# Board.net
KiCad netlist of a schematic drawn in Altium Designer
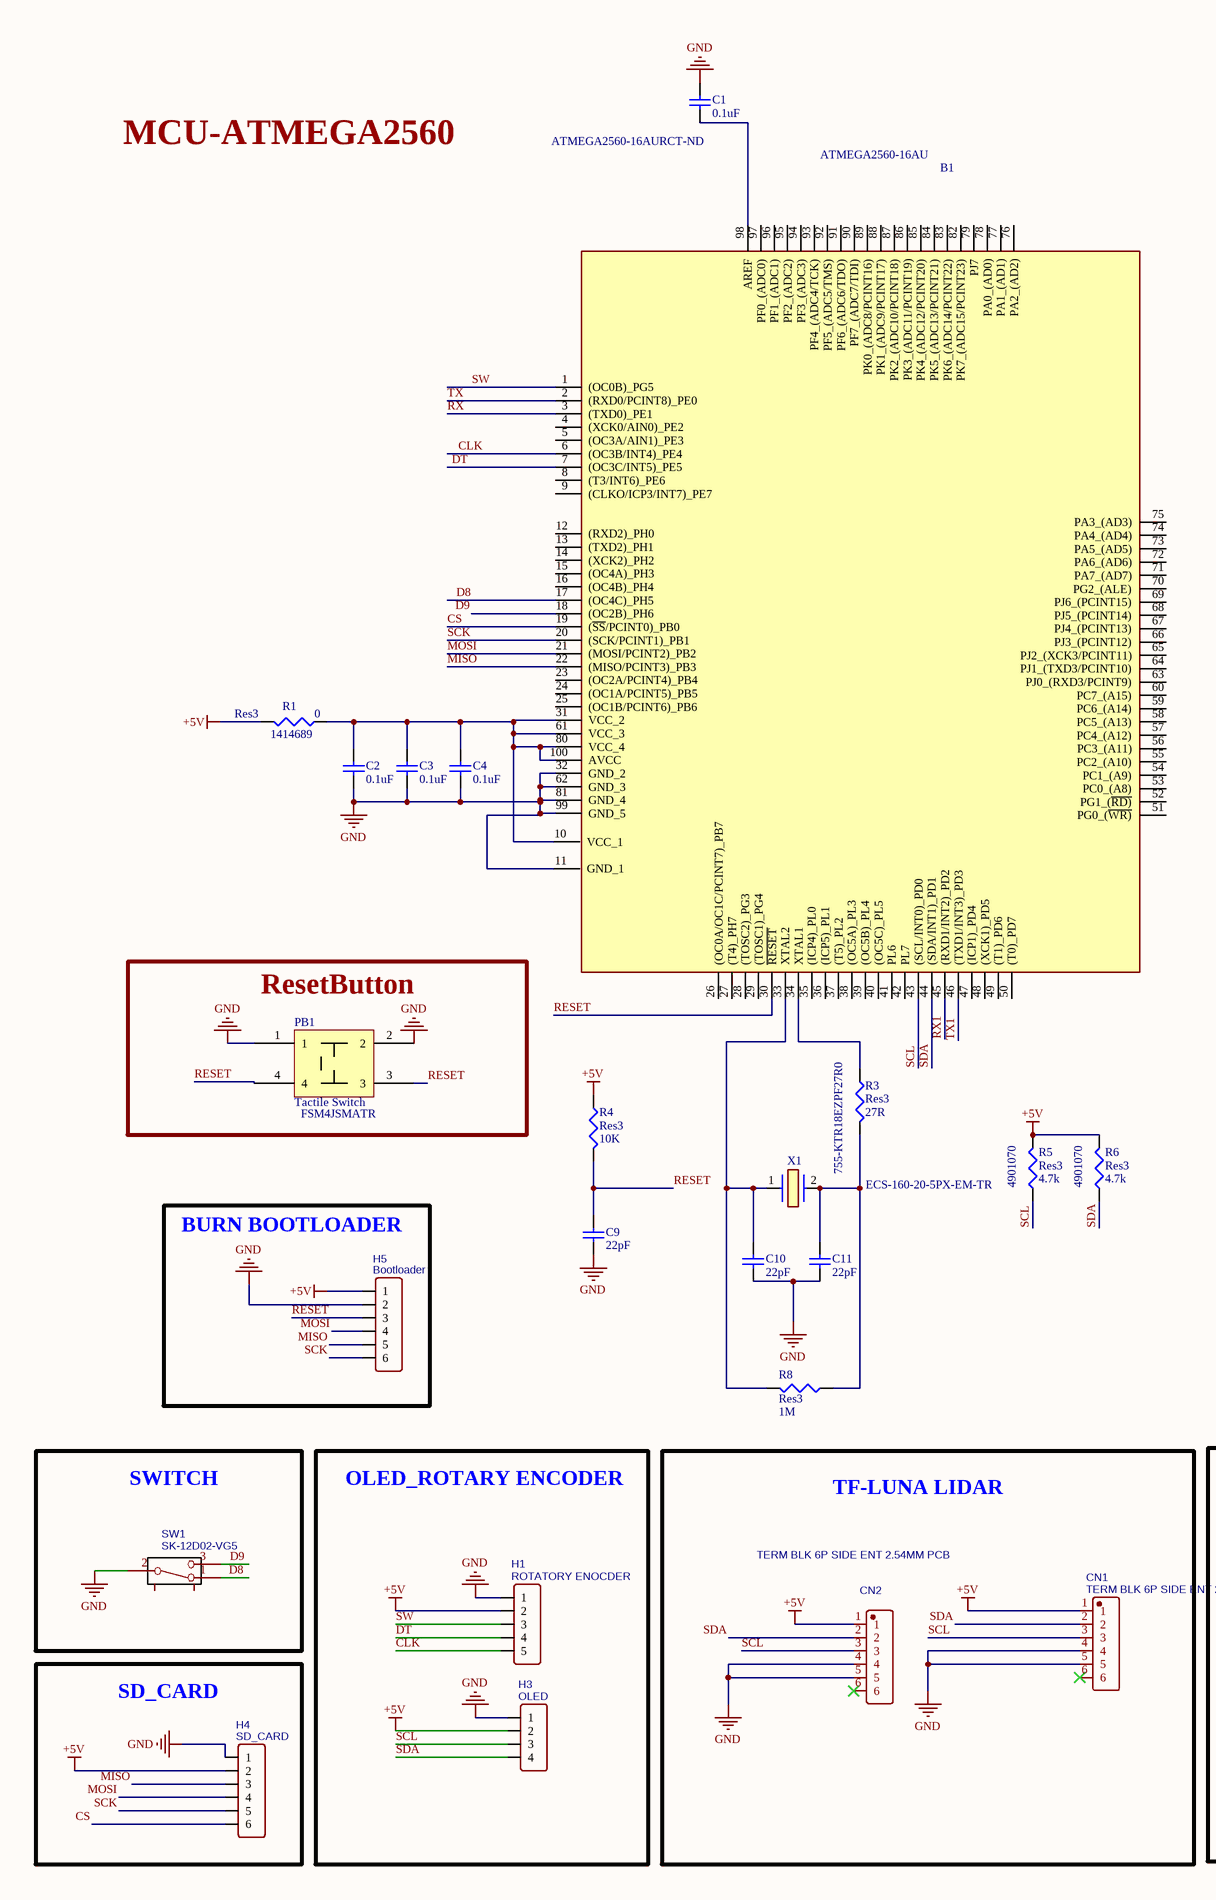
[diagram p0: Board.SchDoc, left]
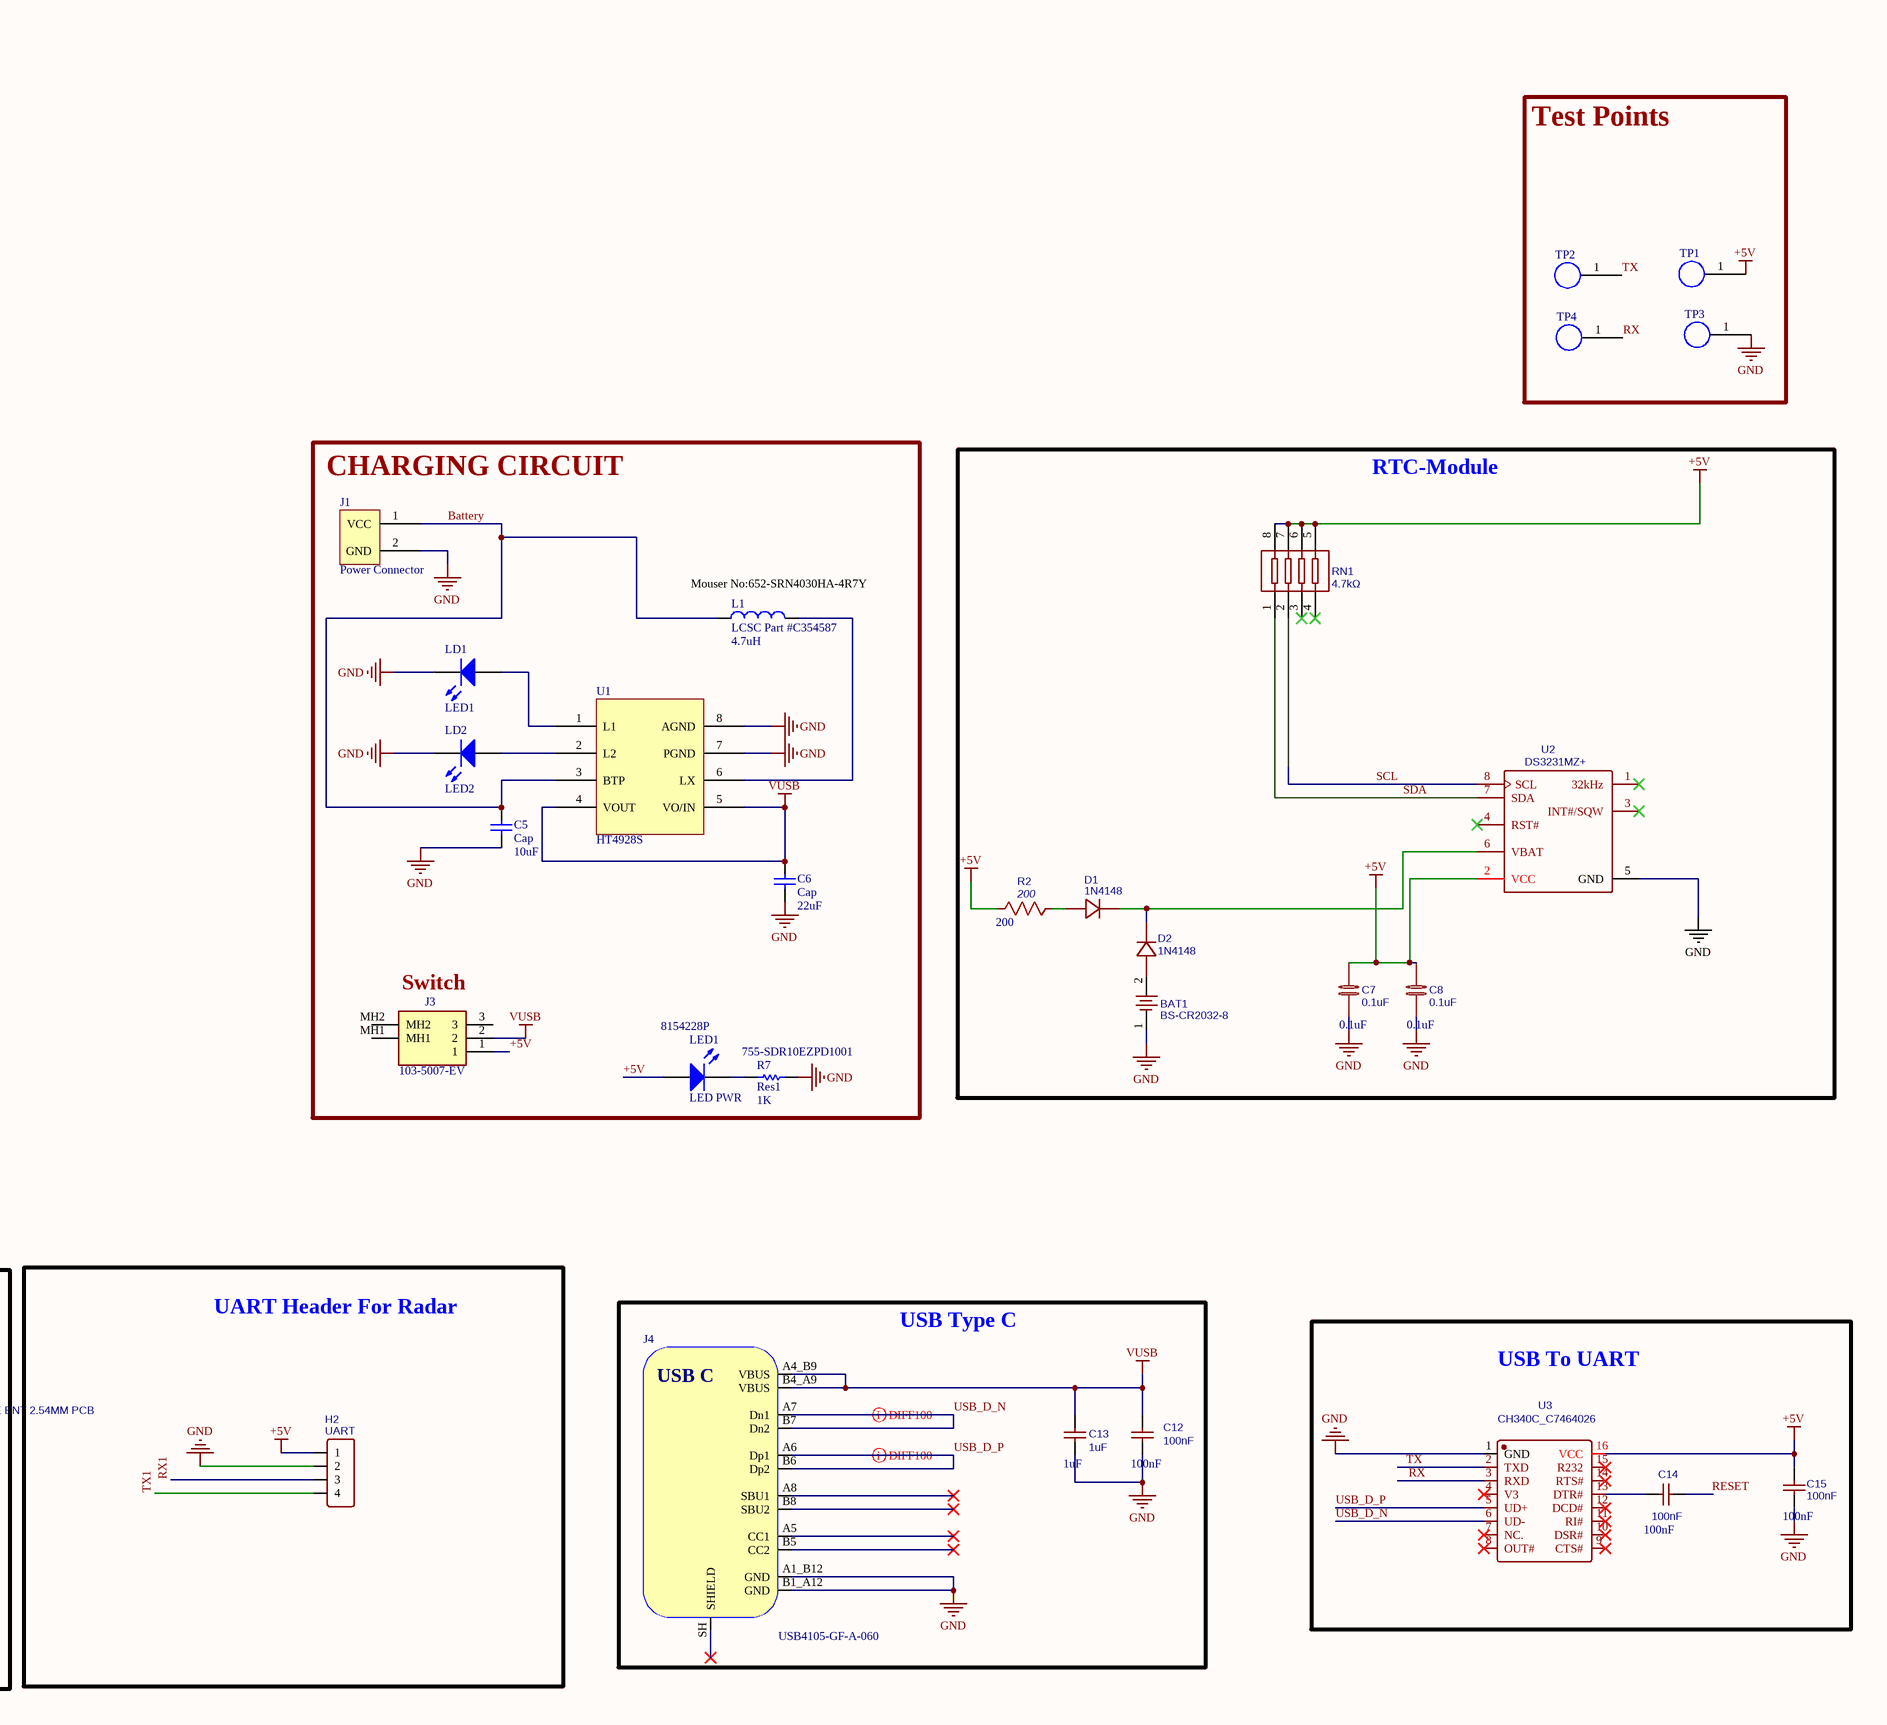
[diagram p1: Board.SchDoc, right]

(export (version "E")
  (design (tool "Eeschema 10.0.6"))
  (components
    (comp (ref "B1")
      (value "ATMEGA2560-16AU")
      (footprint "ATMEGA2560-16AUR")
      (description "AVR ATmega Microcontroller 8-bit 16MHz 256KB FLASH TQFP100")
      (fields
        (field (name "MOUSER PART NUMBER") "556-ATMEGA2560-16AU")
        (field (name "SUPPLIER PART NUMBER 1") "ATMEGA2560-16AURCT-ND")
        (field (name "MANUFACTURER") "Microchip")
      )
      (libsource (lib "aruduino mega_1") (part "ATMEGA2560-16AU"))
    )
    (comp (ref "BAT1")
      (value "BS-CR2032-8")
      (footprint "BS-CR2032-8")
      (fields (field (name "MANUFACTURER") "LX(连欣科技)") (field (name "CONTRIBUTOR") "lcsc"))
      (libsource (lib "altium-import") (part "root_1_BS-CR2032-8_"))
    )
    (comp (ref "C1")
      (value "0.1uF")
      (footprint "CAP 0402")
      (description "Commercial Chip T101 Commercial Tape/reel, 7 Inch Paper Tape")
      (fields
        (field (name "MANUFACTURER") "Kyocera AVX")
        (field (name "MANUFACTURER PART NUMBER") "04023C104KAT2A-62")
      )
      (libsource (lib "Miscellaneous Devices") (part "Cap"))
    )
    (comp (ref "C2")
      (value "0.1uF")
      (footprint "CAP 0402")
      (description "Commercial Chip T101 Commercial Tape/reel, 7 Inch Paper Tape")
      (fields
        (field (name "MANUFACTURER") "Kyocera AVX")
        (field (name "MANUFACTURER PART NUMBER") "04023C104KAT2A-62")
      )
      (libsource (lib "Miscellaneous Devices") (part "Cap"))
    )
    (comp (ref "C3")
      (value "0.1uF")
      (footprint "CAP 0402")
      (description "Commercial Chip T101 Commercial Tape/reel, 7 Inch Paper Tape")
      (fields
        (field (name "MANUFACTURER") "Kyocera AVX")
        (field (name "MANUFACTURER PART NUMBER") "04023C104KAT2A-62")
      )
      (libsource (lib "Miscellaneous Devices") (part "Cap"))
    )
    (comp (ref "C4")
      (value "0.1uF")
      (footprint "CAP 0402")
      (description "Commercial Chip T101 Commercial Tape/reel, 7 Inch Paper Tape")
      (fields
        (field (name "MANUFACTURER") "Kyocera AVX")
        (field (name "MANUFACTURER PART NUMBER") "04023C104KAT2A-62")
      )
      (libsource (lib "Miscellaneous Devices") (part "Cap"))
    )
    (comp (ref "C5")
      (value "Cap")
      (footprint "Cap_0603")
      (description "Capacitor")
      (fields (field (name "ALTIUM_VALUE") "10uF") (field (name "PUBLISHER") "Altium Limited"))
      (libsource (lib "Miscellaneous Devices") (part "Cap"))
    )
    (comp (ref "C6")
      (value "Cap")
      (footprint "CAP 1206")
      (description "Capacitor")
      (fields (field (name "ALTIUM_VALUE") "22uF") (field (name "PUBLISHER") "Altium Limited"))
      (libsource (lib "Miscellaneous Devices") (part "Cap"))
    )
    (comp (ref "C7")
      (value "0.1uF")
      (footprint "CAP_0805")
      (fields
        (field (name "MANUFACTURER PART") "CGA4J3X7T2E104KT0Y0N")
        (field (name "MANUFACTURER") "TDK")
        (field (name "ALTIUM_VALUE") "0.1uF")
        (field (name "CONTRIBUTOR") "LCEDA_Lib")
      )
      (libsource (lib "altium-import") (part "root_1_0.1uF_"))
    )
    (comp (ref "C8")
      (value "0.1uF")
      (footprint "CAP_0805")
      (fields
        (field (name "MANUFACTURER PART") "CGA4J3X7T2E104KT0Y0N")
        (field (name "MANUFACTURER") "TDK")
        (field (name "ALTIUM_VALUE") "0.1uF")
        (field (name "CONTRIBUTOR") "LCEDA_Lib")
      )
      (libsource (lib "altium-import") (part "root_1_0.1uF_"))
    )
    (comp (ref "C9")
      (value "22pF")
      (footprint "CAP 1206")
      (description "22.0Pf 50.0V Rohs Compliant: Yes")
      (fields
        (field (name "MANUFACTURER") "KEMET")
        (field (name "MANUFACTURER PART NUMBER") "C1206C220K5GAC7210")
      )
      (libsource (lib "Miscellaneous Devices") (part "Cap"))
    )
    (comp (ref "C10")
      (value "22pF")
      (footprint "CAP 1206")
      (description "22.0Pf 50.0V Rohs Compliant: Yes")
      (fields
        (field (name "MANUFACTURER") "KEMET")
        (field (name "MANUFACTURER PART NUMBER") "C1206C220K5GAC7210")
      )
      (libsource (lib "Miscellaneous Devices") (part "Cap"))
    )
    (comp (ref "C11")
      (value "22pF")
      (footprint "CAP 1206")
      (description "22.0Pf 50.0V Rohs Compliant: Yes")
      (fields
        (field (name "MANUFACTURER") "KEMET")
        (field (name "MANUFACTURER PART NUMBER") "C1206C220K5GAC7210")
      )
      (libsource (lib "Miscellaneous Devices") (part "Cap"))
    )
    (comp (ref "C12")
      (value "100nF")
      (footprint "Cap_0603")
      (fields
        (field (name "MANUFACTURER PART") "0603B104K160")
        (field (name "MANUFACTURER") "WTC")
        (field (name "ALTIUM_VALUE") "100nF")
      )
      (libsource (lib "altium-import") (part "root_1_100nF_"))
    )
    (comp (ref "C13")
      (value "1uF")
      (footprint "Cap_0603")
      (fields
        (field (name "MANUFACTURER PART") "CL10A105KB8NNNC")
        (field (name "MANUFACTURER") "SAMSUNG")
        (field (name "ALTIUM_VALUE") "1uF")
      )
      (libsource (lib "altium-import") (part "root_1_1uF_"))
    )
    (comp (ref "C14")
      (value "100nF")
      (footprint "Cap_0603")
      (fields
        (field (name "MANUFACTURER PART") "0603B104K160")
        (field (name "MANUFACTURER") "WTC")
        (field (name "ALTIUM_VALUE") "100nF")
      )
      (libsource (lib "altium-import") (part "root_0_100nF_"))
    )
    (comp (ref "C15")
      (value "100nF")
      (footprint "Cap_0603")
      (fields
        (field (name "MANUFACTURER PART") "0603B104K160")
        (field (name "MANUFACTURER") "WTC")
        (field (name "ALTIUM_VALUE") "100nF")
      )
      (libsource (lib "altium-import") (part "root_3_100nF_"))
    )
    (comp (ref "CN1")
      (value "TERM BLK 6P SIDE ENT 2.54MM PCB")
      (footprint "1725698")
      (fields
        (field (name "MANUFACTURER") "Phoenix Contact")
        (field (name "MANUFACTURER PART") "1725698")
        (field (name "CONTRIBUTOR") "waqasalivicky123")
      )
      (libsource (lib "altium-import") (part "root_3_6 pin JST_"))
    )
    (comp (ref "CN2")
      (value "TERM BLK 6P SIDE ENT 2.54MM PCB")
      (footprint "1725698")
      (fields
        (field (name "MANUFACTURER") "Phoenix Contact")
        (field (name "MANUFACTURER PART") "1725698")
        (field (name "CONTRIBUTOR") "waqasalivicky123")
      )
      (libsource (lib "altium-import") (part "root_3_6 pin JST_"))
    )
    (comp (ref "D1")
      (value "1N4148")
      (footprint "1N4148WS")
      (fields (field (name "MANUFACTURER") "LJ(朗捷)") (field (name "CONTRIBUTOR") "lcsc"))
      (libsource (lib "altium-import") (part "root_0_1N4148_C18195411_"))
    )
    (comp (ref "D2")
      (value "1N4148")
      (footprint "1N4148WS")
      (fields (field (name "MANUFACTURER") "LJ(朗捷)") (field (name "CONTRIBUTOR") "lcsc"))
      (libsource (lib "altium-import") (part "root_1_1N4148_C18195411_"))
    )
    (comp (ref "H1")
      (value "ROTATORY ENOCDER")
      (footprint "HDR 1X5")
      (fields (field (name "CONTRIBUTOR") "LCEDA_Lib"))
      (libsource (lib "altium-import") (part "root_0_ROTATORY ENOCDER_"))
    )
    (comp (ref "H2")
      (value "UART")
      (footprint "H2")
      (fields (field (name "CONTRIBUTOR") "LCEDA_Lib"))
      (libsource (lib "altium-import") (part "root_0_OLED_"))
    )
    (comp (ref "H3")
      (value "OLED")
      (footprint "HDR 1X4")
      (fields (field (name "CONTRIBUTOR") "LCEDA_Lib"))
      (libsource (lib "altium-import") (part "root_0_OLED_"))
    )
    (comp (ref "H4")
      (value "SD_CARD")
      (footprint "HDR 1X6")
      (fields (field (name "CONTRIBUTOR") "LCEDA_Lib"))
      (libsource (lib "altium-import") (part "root_0_SD_CARD_"))
    )
    (comp (ref "H5")
      (value "Bootloader")
      (footprint "HDR 1X6")
      (fields (field (name "CONTRIBUTOR") "LCEDA_Lib"))
      (libsource (lib "altium-import") (part "root_0_SD_CARD_"))
    )
    (comp (ref "J1")
      (value "Power Connector")
      (footprint "1725656")
      (description "TERM BLK 2P SIDE ENT 2.54MM PCB")
      (fields (field (name "MANUFACTURER") "Phoenix Contact"))
      (libsource (lib "Schlib1") (part "Power Connector"))
    )
    (comp (ref "J3")
      (value "103-5007-EV")
      (footprint "1035007EV")
      (description "Switch")
      (libsource (lib "*") (part "103-5007-EV"))
    )
    (comp (ref "J4")
      (value "USB4105-GF-A-060")
      (footprint "USB4105GFA060")
      (description "USB Connector Type C SMT 12 Pin")
      (fields (field (name "MANUFACTURER") "GCT"))
      (libsource (lib "Schematic-Lib-PhilsLab") (part "USB4105-GF-A-060"))
    )
    (comp (ref "L1")
      (value "LCSC Part #C354587")
      (footprint "L1")
      (description "Inductor")
      (fields (field (name "ALTIUM_VALUE") "4.7uH") (field (name "PUBLISHER") "Altium Limited"))
      (libsource (lib "Miscellaneous Devices") (part "Inductor"))
    )
    (comp (ref "LD1")
      (value "LED1")
      (footprint "0603-LED")
      (description "Typical RED, GREEN, YELLOW, AMBER GaAs LED")
      (fields (field (name "PUBLISHER") "Altium Limited"))
      (libsource (lib "Miscellaneous Devices") (part "LED2"))
    )
    (comp (ref "LD2")
      (value "LED2")
      (footprint "0603-LED")
      (description "Typical RED, GREEN, YELLOW, AMBER GaAs LED")
      (fields (field (name "PUBLISHER") "Altium Limited"))
      (libsource (lib "Miscellaneous Devices") (part "LED2"))
    )
    (comp (ref "LED1")
      (value "LED PWR")
      (footprint "0603-LED")
      (description "Led, Blue, 470 Nm, 3.2 V, 30 Ma, 145 Mcd Rohs Compliant: Yes ¦Wurth Elektronik 150080BS75000")
      (fields
        (field (name "SUPPLIER PART NUMBER 1") "8154228P")
        (field (name "MANUFACTURER") "Wurth Electronics")
        (field (name "MANUFACTURER PART NUMBER") "150080BS75000")
        (field (name "PUBLISHER") "Altium Limited")
      )
      (libsource (lib "Miscellaneous Devices") (part "LED0"))
    )
    (comp (ref "PB1")
      (value "Tactile Switch")
      (footprint "PB1")
      (description "Switch Tactile OFF (ON) SPST Round Button Gull Wing 0.05A 24VDC 1.57N SMD T/R")
      (fields
        (field (name "SUPPLIER PART NUMBER 1") "FSM4JSMATR")
        (field (name "MANUFACTURER") "TE Connectivity Alcoswitch")
        (field (name "MANUFACTURER PART NUMBER") "FSM4JSMATR")
      )
      (libsource (lib "CoinAccepter_1") (part "Tactile Switch"))
    )
    (comp (ref "R1")
      (value "Res3")
      (footprint "1206-res")
      (description "RES SMD 0 OHM JUMPER 1/4W 1206")
      (fields
        (field (name "ALTIUM_VALUE") "0")
        (field (name "SUPPLIER PART NUMBER 1") "1414689")
        (field (name "MANUFACTURER") "Yageo")
        (field (name "MANUFACTURER PART NUMBER") "RC1206JR-070RL")
        (field (name "PUBLISHER") "Altium Limited")
      )
      (libsource (lib "Miscellaneous Devices") (part "Res3"))
    )
    (comp (ref "R2")
      (value "200")
      (footprint "Res_0805")
      (fields
        (field (name "MANUFACTURER PART") "PTFR0805Q200RN9")
        (field (name "MANUFACTURER") "RESI(开步睿思)")
        (field (name "ALTIUM_VALUE") "200")
        (field (name "CONTRIBUTOR") "LCEDA_Lib")
      )
      (libsource (lib "altium-import") (part "root_0_200_"))
    )
    (comp (ref "R3")
      (value "Res3")
      (footprint "1206-res")
      (description "Res Thick Film 1206 27 Ohm 1% 0.25W(1/4W) ±100ppm/C Pad SMD Automotive T/R")
      (fields
        (field (name "ALTIUM_VALUE") "27R")
        (field (name "SUPPLIER PART NUMBER 1") "755-KTR18EZPF27R0")
        (field (name "MANUFACTURER") "Rohm")
        (field (name "MANUFACTURER PART NUMBER") "KTR18EZPF27R0")
      )
      (libsource (lib "Miscellaneous Devices") (part "Res3"))
    )
    (comp (ref "R4")
      (value "Res3")
      (footprint "1206-res")
      (description "Lead Free Chip Resistor Thick Film 1206 10kOhm 5% Paper T/R")
      (fields
        (field (name "ALTIUM_VALUE") "10K")
        (field (name "MANUFACTURER") "Yageo")
        (field (name "MANUFACTURER PART NUMBER") "RC1206JR-0710KP")
      )
      (libsource (lib "Miscellaneous Devices") (part "Res3"))
    )
    (comp (ref "R5")
      (value "Res3")
      (footprint "1206-res")
      (description "Res Thick Film 1206 4.7K Ohm 5% 1/4W ¦100ppm/¦C SMD Paper T/R")
      (fields
        (field (name "ALTIUM_VALUE") "4.7k")
        (field (name "SUPPLIER PART NUMBER 1") "4901070")
        (field (name "MANUFACTURER") "Yageo")
        (field (name "MANUFACTURER PART NUMBER") "RC1206JR-074K7L")
      )
      (libsource (lib "Miscellaneous Devices") (part "Res3"))
    )
    (comp (ref "R6")
      (value "Res3")
      (footprint "1206-res")
      (description "Res Thick Film 1206 4.7K Ohm 5% 1/4W ¦100ppm/¦C SMD Paper T/R")
      (fields
        (field (name "ALTIUM_VALUE") "4.7k")
        (field (name "SUPPLIER PART NUMBER 1") "4901070")
        (field (name "MANUFACTURER") "Yageo")
        (field (name "MANUFACTURER PART NUMBER") "RC1206JR-074K7L")
      )
      (libsource (lib "Miscellaneous Devices") (part "Res3"))
    )
    (comp (ref "R7")
      (value "Res1")
      (footprint "Res_0805")
      (description "Resistor")
      (fields
        (field (name "ALTIUM_VALUE") "1K")
        (field (name "SUPPLIER PART NUMBER 1") "755-SDR10EZPD1001")
        (field (name "MANUFACTURER") "Rohm")
        (field (name "MANUFACTURER PART NUMBER") "SDR10EZPD1001")
        (field (name "PUBLISHER") "Altium Limited")
      )
      (libsource (lib "Miscellaneous Devices") (part "Res1"))
    )
    (comp (ref "R8")
      (value "Res3")
      (footprint "1206-res")
      (description "Res Thick Film 1206 1M Ohm 5% 0.25W(1/4W) ±100ppm/C Pad SMD Automotive T/R")
      (fields
        (field (name "ALTIUM_VALUE") "1M")
        (field (name "MANUFACTURER") "Yageo")
        (field (name "MANUFACTURER PART NUMBER") "AC1206JR-071ML")
      )
      (libsource (lib "Miscellaneous Devices") (part "Res3"))
    )
    (comp (ref "RN1")
      (value "4.7kΩ")
      (footprint "WA04X472JTL")
      (fields
        (field (name "MANUFACTURER") "Walsin(华新科)")
        (field (name "MANUFACTURER PART") "WA04X472JTL")
        (field (name "CONTRIBUTOR") "LCSC")
      )
      (libsource (lib "altium-import") (part "root_0_4.7kΩ_"))
    )
    (comp (ref "SW1")
      (value "SK-12D02-VG5")
      (footprint "SK12D02GA42S")
      (fields (field (name "MANUFACTURER") "韩国韩荣") (field (name "CONTRIBUTOR") "LCSC"))
      (libsource (lib "altium-import") (part "root_0_SK-12D02-VG5_"))
    )
    (comp (ref "TP1") (value "~") (footprint "TP") (libsource (lib "TestPoint") (part "Component_1")))
    (comp (ref "TP2") (value "~") (footprint "TP") (libsource (lib "TestPoint") (part "Component_1")))
    (comp (ref "TP3") (value "~") (footprint "TP") (libsource (lib "TestPoint") (part "Component_1")))
    (comp (ref "TP4") (value "~") (footprint "TP") (libsource (lib "TestPoint") (part "Component_1")))
    (comp (ref "U1")
      (value "HT4928S")
      (footprint "DS3231MZ+TRL")
      (libsource (lib "Schlib1") (part "HT4928S"))
    )
    (comp (ref "U2")
      (value "DS3231MZ+")
      (footprint "DS3231MZ+TRL")
      (fields
        (field (name "MANUFACTURER") "ADI(亚德诺)/MAXIM(美信)")
        (field (name "MANUFACTURER PART") "DS3231MZ+TRL")
      )
      (libsource (lib "altium-import") (part "root_0_DS3231MZ+_"))
    )
    (comp (ref "U3")
      (value "CH340C_C7464026")
      (footprint "CH340C")
      (fields
        (field (name "MANUFACTURER") "WCH(南京沁恒)")
        (field (name "MANUFACTURER PART") "CH340C")
        (field (name "CONTRIBUTOR") "lcsc")
      )
      (libsource (lib "altium-import") (part "root_0_CH340C_C7464026_"))
    )
    (comp (ref "X1")
      (value "ECS-160-20-5PX-EM-TR")
      (footprint "X1")
      (description "Crystal 16.0000MHZ 20PF SMD")
      (fields (field (name "MANUFACTURER") "ECS International"))
      (libsource (lib "*") (part "ABS05-32.768KHZ-6-T"))
    )
  )
  (nets
    (net (code "1") (name "+5V") (class "Default")
      (node (ref "C15") (pin "1") (pinfunction "1_1") (pintype "passive"))
      (node (ref "C7") (pin "2") (pinfunction "2_2") (pintype "passive"))
      (node (ref "C8") (pin "2") (pinfunction "2_2") (pintype "passive"))
      (node (ref "CN1") (pin "1") (pinfunction "1_1") (pintype "passive"))
      (node (ref "CN2") (pin "1") (pinfunction "1_1") (pintype "passive"))
      (node (ref "H1") (pin "2") (pinfunction "2_2") (pintype "passive"))
      (node (ref "H2") (pin "1") (pinfunction "1_1") (pintype "passive"))
      (node (ref "H3") (pin "2") (pinfunction "2_2") (pintype "passive"))
      (node (ref "H4") (pin "2") (pinfunction "2_2") (pintype "passive"))
      (node (ref "H5") (pin "1") (pinfunction "1_1") (pintype "passive"))
      (node (ref "J3") (pin "1") (pinfunction "1_1") (pintype "passive"))
      (node (ref "LED1") (pin "1") (pinfunction "A_1") (pintype "passive"))
      (node (ref "R1") (pin "2") (pinfunction "2_2") (pintype "passive"))
      (node (ref "R2") (pin "1") (pinfunction "1_1") (pintype "passive"))
      (node (ref "R4") (pin "1") (pinfunction "1_1") (pintype "passive"))
      (node (ref "R5") (pin "2") (pinfunction "2_2") (pintype "passive"))
      (node (ref "R6") (pin "2") (pinfunction "2_2") (pintype "passive"))
      (node (ref "RN1") (pin "5") (pinfunction "5_5") (pintype "passive"))
      (node (ref "RN1") (pin "6") (pinfunction "6_6") (pintype "passive"))
      (node (ref "RN1") (pin "7") (pinfunction "7_7") (pintype "passive"))
      (node (ref "RN1") (pin "8") (pinfunction "8_8") (pintype "passive"))
      (node (ref "TP1") (pin "1") (pinfunction "TP_1") (pintype "passive"))
      (node (ref "U2") (pin "2") (pinfunction "VCC_2") (pintype "passive"))
      (node (ref "U3") (pin "16") (pinfunction "VCC_16") (pintype "passive"))
    )
    (net (code "2") (name "/Battery") (class "Default")
      (node (ref "C5") (pin "1") (pinfunction "1_1") (pintype "passive"))
      (node (ref "J1") (pin "1") (pinfunction "VCC_1") (pintype "passive"))
      (node (ref "L1") (pin "1") (pinfunction "1_1") (pintype "passive"))
      (node (ref "U1") (pin "3") (pinfunction "BTP_3") (pintype "passive"))
    )
    (net (code "3") (name "/CLK") (class "Default")
      (node (ref "B1") (pin "6") (pinfunction "(OC3B/INT4)_PE4_6") (pintype "passive"))
      (node (ref "H1") (pin "5") (pinfunction "5_5") (pintype "passive"))
    )
    (net (code "4") (name "/CS") (class "Default")
      (node (ref "B1") (pin "19") (pinfunction "(~{SS}/PCINT0)_PB0_19") (pintype "passive"))
      (node (ref "H4") (pin "6") (pinfunction "6_6") (pintype "passive"))
    )
    (net (code "5") (name "/D8") (class "Default")
      (node (ref "B1") (pin "17") (pinfunction "(OC4C)_PH5_17") (pintype "passive"))
      (node (ref "SW1") (pin "1") (pinfunction "1_1") (pintype "passive"))
    )
    (net (code "6") (name "/D9") (class "Default")
      (node (ref "B1") (pin "18") (pinfunction "(OC2B)_PH6_18") (pintype "passive"))
      (node (ref "SW1") (pin "3") (pinfunction "3_3") (pintype "passive"))
    )
    (net (code "7") (name "/DT") (class "Default")
      (node (ref "B1") (pin "7") (pinfunction "(OC3C/INT5)_PE5_7") (pintype "passive"))
      (node (ref "H1") (pin "4") (pinfunction "4_4") (pintype "passive"))
    )
    (net (code "8") (name "/MISO") (class "Default")
      (node (ref "B1") (pin "22") (pinfunction "(MISO/PCINT3)_PB3_22") (pintype "passive"))
      (node (ref "H4") (pin "3") (pinfunction "3_3") (pintype "passive"))
      (node (ref "H5") (pin "5") (pinfunction "5_5") (pintype "passive"))
    )
    (net (code "9") (name "/MOSI") (class "Default")
      (node (ref "B1") (pin "21") (pinfunction "(MOSI/PCINT2)_PB2_21") (pintype "passive"))
      (node (ref "H4") (pin "4") (pinfunction "4_4") (pintype "passive"))
      (node (ref "H5") (pin "4") (pinfunction "4_4") (pintype "passive"))
    )
    (net (code "10") (name "/RESET") (class "Default")
      (node (ref "B1") (pin "30") (pinfunction "~{RESET}_30") (pintype "passive"))
      (node (ref "C14") (pin "2") (pinfunction "2_2") (pintype "passive"))
      (node (ref "C9") (pin "1") (pinfunction "1_1") (pintype "passive"))
      (node (ref "H5") (pin "3") (pinfunction "3_3") (pintype "passive"))
      (node (ref "PB1") (pin "3") (pinfunction "3_3") (pintype "passive"))
      (node (ref "PB1") (pin "4") (pinfunction "4_4") (pintype "passive"))
      (node (ref "R4") (pin "2") (pinfunction "2_2") (pintype "passive"))
    )
    (net (code "11") (name "/RX") (class "Default")
      (node (ref "B1") (pin "3") (pinfunction "(TXD0)_PE1_3") (pintype "passive"))
      (node (ref "TP4") (pin "1") (pinfunction "TP_1") (pintype "passive"))
      (node (ref "U3") (pin "3") (pinfunction "RXD_3") (pintype "passive"))
    )
    (net (code "12") (name "/RX1") (class "Default")
      (node (ref "B1") (pin "45") (pinfunction "(RXD1/INT2)_PD2_45") (pintype "passive"))
      (node (ref "H2") (pin "3") (pinfunction "3_3") (pintype "passive"))
    )
    (net (code "13") (name "/SCK") (class "Default")
      (node (ref "B1") (pin "20") (pinfunction "(SCK/PCINT1)_PB1_20") (pintype "passive"))
      (node (ref "H4") (pin "5") (pinfunction "5_5") (pintype "passive"))
      (node (ref "H5") (pin "6") (pinfunction "6_6") (pintype "passive"))
    )
    (net (code "14") (name "/SCL") (class "Default")
      (node (ref "B1") (pin "43") (pinfunction "(SCL/INT0)_PD0_43") (pintype "passive"))
      (node (ref "CN1") (pin "3") (pinfunction "3_3") (pintype "passive"))
      (node (ref "CN2") (pin "3") (pinfunction "3_3") (pintype "passive"))
      (node (ref "H3") (pin "3") (pinfunction "3_3") (pintype "passive"))
      (node (ref "R5") (pin "1") (pinfunction "1_1") (pintype "passive"))
      (node (ref "RN1") (pin "2") (pinfunction "2_2") (pintype "passive"))
      (node (ref "U2") (pin "8") (pinfunction "SCL_8") (pintype "passive"))
    )
    (net (code "15") (name "/SDA") (class "Default")
      (node (ref "B1") (pin "44") (pinfunction "(SDA/INT1)_PD1_44") (pintype "passive"))
      (node (ref "CN1") (pin "2") (pinfunction "2_2") (pintype "passive"))
      (node (ref "CN2") (pin "2") (pinfunction "2_2") (pintype "passive"))
      (node (ref "H3") (pin "4") (pinfunction "4_4") (pintype "passive"))
      (node (ref "R6") (pin "1") (pinfunction "1_1") (pintype "passive"))
      (node (ref "RN1") (pin "1") (pinfunction "1_1") (pintype "passive"))
      (node (ref "U2") (pin "7") (pinfunction "SDA_7") (pintype "passive"))
    )
    (net (code "16") (name "/SW") (class "Default")
      (node (ref "B1") (pin "1") (pinfunction "(OC0B)_PG5_1") (pintype "passive"))
      (node (ref "H1") (pin "3") (pinfunction "3_3") (pintype "passive"))
    )
    (net (code "17") (name "/TX") (class "Default")
      (node (ref "B1") (pin "2") (pinfunction "(RXD0/PCINT8)_PE0_2") (pintype "passive"))
      (node (ref "TP2") (pin "1") (pinfunction "TP_1") (pintype "passive"))
      (node (ref "U3") (pin "2") (pinfunction "TXD_2") (pintype "passive"))
    )
    (net (code "18") (name "/TX1") (class "Default")
      (node (ref "B1") (pin "46") (pinfunction "(TXD1/INT3)_PD3_46") (pintype "passive"))
      (node (ref "H2") (pin "4") (pinfunction "4_4") (pintype "passive"))
    )
    (net (code "19") (name "/USB_D_N") (class "Default")
      (node (ref "J4") (pin "A7") (pinfunction "Dn1_A7") (pintype "passive"))
      (node (ref "J4") (pin "B7") (pinfunction "Dn2_B7") (pintype "passive"))
      (node (ref "U3") (pin "6") (pinfunction "UD-_6") (pintype "passive"))
    )
    (net (code "20") (name "/USB_D_P") (class "Default")
      (node (ref "J4") (pin "A6") (pinfunction "Dp1_A6") (pintype "passive"))
      (node (ref "J4") (pin "B6") (pinfunction "Dp2_B6") (pintype "passive"))
      (node (ref "U3") (pin "5") (pinfunction "UD+_5") (pintype "passive"))
    )
    (net (code "21") (name "GND") (class "Default")
      (node (ref "B1") (pin "11") (pinfunction "GND_1_11") (pintype "passive"))
      (node (ref "B1") (pin "32") (pinfunction "GND_2_32") (pintype "passive"))
      (node (ref "B1") (pin "62") (pinfunction "GND_3_62") (pintype "passive"))
      (node (ref "B1") (pin "81") (pinfunction "GND_4_81") (pintype "passive"))
      (node (ref "B1") (pin "99") (pinfunction "GND_5_99") (pintype "passive"))
      (node (ref "BAT1") (pin "1") (pinfunction "1_1") (pintype "passive"))
      (node (ref "C1") (pin "1") (pinfunction "1_1") (pintype "passive"))
      (node (ref "C10") (pin "2") (pinfunction "2_2") (pintype "passive"))
      (node (ref "C11") (pin "2") (pinfunction "2_2") (pintype "passive"))
      (node (ref "C12") (pin "1") (pinfunction "1_1") (pintype "passive"))
      (node (ref "C13") (pin "1") (pinfunction "1_1") (pintype "passive"))
      (node (ref "C15") (pin "2") (pinfunction "2_2") (pintype "passive"))
      (node (ref "C2") (pin "2") (pinfunction "2_2") (pintype "passive"))
      (node (ref "C3") (pin "2") (pinfunction "2_2") (pintype "passive"))
      (node (ref "C4") (pin "2") (pinfunction "2_2") (pintype "passive"))
      (node (ref "C5") (pin "2") (pinfunction "2_2") (pintype "passive"))
      (node (ref "C6") (pin "2") (pinfunction "2_2") (pintype "passive"))
      (node (ref "C7") (pin "1") (pinfunction "1_1") (pintype "passive"))
      (node (ref "C8") (pin "1") (pinfunction "1_1") (pintype "passive"))
      (node (ref "C9") (pin "2") (pinfunction "2_2") (pintype "passive"))
      (node (ref "CN1") (pin "4") (pinfunction "4_4") (pintype "passive"))
      (node (ref "CN1") (pin "5") (pinfunction "5_5") (pintype "passive"))
      (node (ref "CN2") (pin "4") (pinfunction "4_4") (pintype "passive"))
      (node (ref "CN2") (pin "5") (pinfunction "5_5") (pintype "passive"))
      (node (ref "H1") (pin "1") (pinfunction "1_1") (pintype "passive"))
      (node (ref "H2") (pin "2") (pinfunction "2_2") (pintype "passive"))
      (node (ref "H3") (pin "1") (pinfunction "1_1") (pintype "passive"))
      (node (ref "H4") (pin "1") (pinfunction "1_1") (pintype "passive"))
      (node (ref "H5") (pin "2") (pinfunction "2_2") (pintype "passive"))
      (node (ref "J1") (pin "2") (pinfunction "GND_2") (pintype "passive"))
      (node (ref "J4") (pin "A1_B12") (pinfunction "GND_A1_B12") (pintype "passive"))
      (node (ref "J4") (pin "B1_A12") (pinfunction "GND_B1_A12") (pintype "passive"))
      (node (ref "LD1") (pin "2") (pinfunction "K_2") (pintype "passive"))
      (node (ref "LD2") (pin "2") (pinfunction "K_2") (pintype "passive"))
      (node (ref "PB1") (pin "1") (pinfunction "1_1") (pintype "passive"))
      (node (ref "PB1") (pin "2") (pinfunction "2_2") (pintype "passive"))
      (node (ref "R7") (pin "1") (pinfunction "1_1") (pintype "passive"))
      (node (ref "SW1") (pin "2") (pinfunction "2_2") (pintype "passive"))
      (node (ref "TP3") (pin "1") (pinfunction "TP_1") (pintype "passive"))
      (node (ref "U1") (pin "7") (pinfunction "PGND_7") (pintype "passive"))
      (node (ref "U1") (pin "8") (pinfunction "AGND_8") (pintype "passive"))
      (node (ref "U2") (pin "5") (pinfunction "GND_5") (pintype "passive"))
      (node (ref "U3") (pin "1") (pinfunction "GND_1") (pintype "passive"))
    )
    (net (code "22") (name "Net-(B1-AREF)") (class "Default")
      (node (ref "B1") (pin "98") (pinfunction "AREF_98") (pintype "passive"))
      (node (ref "C1") (pin "2") (pinfunction "2_2") (pintype "passive"))
    )
    (net (code "23") (name "Net-(B1-AVCC)") (class "Default")
      (node (ref "B1") (pin "10") (pinfunction "VCC_1_10") (pintype "passive"))
      (node (ref "B1") (pin "100") (pinfunction "AVCC_100") (pintype "passive"))
      (node (ref "B1") (pin "31") (pinfunction "VCC_2_31") (pintype "passive"))
      (node (ref "B1") (pin "61") (pinfunction "VCC_3_61") (pintype "passive"))
      (node (ref "B1") (pin "80") (pinfunction "VCC_4_80") (pintype "passive"))
      (node (ref "C2") (pin "1") (pinfunction "1_1") (pintype "passive"))
      (node (ref "C3") (pin "1") (pinfunction "1_1") (pintype "passive"))
      (node (ref "C4") (pin "1") (pinfunction "1_1") (pintype "passive"))
      (node (ref "R1") (pin "1") (pinfunction "1_1") (pintype "passive"))
    )
    (net (code "24") (name "Net-(B1-XTAL1)") (class "Default")
      (node (ref "B1") (pin "34") (pinfunction "XTAL1_34") (pintype "passive"))
      (node (ref "R3") (pin "1") (pinfunction "1_1") (pintype "passive"))
    )
    (net (code "25") (name "Net-(B1-XTAL2)") (class "Default")
      (node (ref "B1") (pin "33") (pinfunction "XTAL2_33") (pintype "passive"))
      (node (ref "C10") (pin "1") (pinfunction "1_1") (pintype "passive"))
      (node (ref "R8") (pin "2") (pinfunction "2_2") (pintype "passive"))
      (node (ref "X1") (pin "1") (pintype "passive"))
    )
    (net (code "26") (name "Net-(D1-A)") (class "Default")
      (node (ref "D1") (pin "1") (pinfunction "A_1") (pintype "passive"))
      (node (ref "R2") (pin "2") (pinfunction "2_2") (pintype "passive"))
    )
    (net (code "27") (name "Net-(D1-C)") (class "Default")
      (node (ref "D1") (pin "2") (pinfunction "C_2") (pintype "passive"))
      (node (ref "D2") (pin "2") (pinfunction "C_2") (pintype "passive"))
      (node (ref "U2") (pin "6") (pinfunction "VBAT_6") (pintype "passive"))
    )
    (net (code "28") (name "Net-(D2-A)") (class "Default")
      (node (ref "BAT1") (pin "2") (pinfunction "2_2") (pintype "passive"))
      (node (ref "D2") (pin "1") (pinfunction "A_1") (pintype "passive"))
    )
    (net (code "29") (name "Net-(LD1-A)") (class "Default")
      (node (ref "LD1") (pin "1") (pinfunction "A_1") (pintype "passive"))
      (node (ref "U1") (pin "1") (pinfunction "L1_1") (pintype "passive"))
    )
    (net (code "30") (name "Net-(LD2-A)") (class "Default")
      (node (ref "LD2") (pin "1") (pinfunction "A_1") (pintype "passive"))
      (node (ref "U1") (pin "2") (pinfunction "L2_2") (pintype "passive"))
    )
    (net (code "31") (name "Net-(LED1-K)") (class "Default")
      (node (ref "LED1") (pin "2") (pinfunction "K_2") (pintype "passive"))
      (node (ref "R7") (pin "2") (pinfunction "2_2") (pintype "passive"))
    )
    (net (code "32") (name "Net-(U1-LX)") (class "Default")
      (node (ref "L1") (pin "2") (pinfunction "2_2") (pintype "passive"))
      (node (ref "U1") (pin "6") (pinfunction "LX_6") (pintype "passive"))
    )
    (net (code "33") (name "Net-(U3-DTR#)") (class "Default")
      (node (ref "C14") (pin "1") (pinfunction "1_1") (pintype "passive"))
      (node (ref "U3") (pin "13") (pinfunction "DTR#_13") (pintype "passive"))
    )
    (net (code "34") (name "Net-(X1-CRYSTAL__2)") (class "Default")
      (node (ref "C11") (pin "1") (pinfunction "1_1") (pintype "passive"))
      (node (ref "R3") (pin "2") (pinfunction "2_2") (pintype "passive"))
      (node (ref "R8") (pin "1") (pinfunction "1_1") (pintype "passive"))
      (node (ref "X1") (pin "2") (pinfunction "CRYSTAL__2_2") (pintype "passive"))
    )
    (net (code "35") (name "VUSB") (class "Default")
      (node (ref "C12") (pin "2") (pinfunction "2_2") (pintype "passive"))
      (node (ref "C13") (pin "2") (pinfunction "2_2") (pintype "passive"))
      (node (ref "C6") (pin "1") (pinfunction "1_1") (pintype "passive"))
      (node (ref "J3") (pin "2") (pinfunction "2_2") (pintype "passive"))
      (node (ref "J4") (pin "A4_B9") (pinfunction "VBUS_A4_B9") (pintype "passive"))
      (node (ref "J4") (pin "B4_A9") (pinfunction "VBUS_B4_A9") (pintype "passive"))
      (node (ref "U1") (pin "4") (pinfunction "VOUT_4") (pintype "passive"))
      (node (ref "U1") (pin "5") (pinfunction "VO/IN_5") (pintype "passive"))
    )
    (net (code "36") (name "unconnected-(B1-(CLKO{slash}ICP3{slash}INT7)_PE7-Pad9)") (class "Default")
      (node (ref "B1") (pin "9") (pinfunction "(CLKO/ICP3/INT7)_PE7_9") (pintype "passive"))
    )
    (net (code "37") (name "unconnected-(B1-(ICP1)_PD4-Pad47)") (class "Default")
      (node (ref "B1") (pin "47") (pinfunction "(ICP1)_PD4_47") (pintype "passive"))
    )
    (net (code "38") (name "unconnected-(B1-(ICP4)_PL0-Pad35)") (class "Default")
      (node (ref "B1") (pin "35") (pinfunction "(ICP4)_PL0_35") (pintype "passive"))
    )
    (net (code "39") (name "unconnected-(B1-(ICP5)_PL1-Pad36)") (class "Default")
      (node (ref "B1") (pin "36") (pinfunction "(ICP5)_PL1_36") (pintype "passive"))
    )
    (net (code "40") (name "unconnected-(B1-(OC0A{slash}OC1C{slash}PCINT7)_PB7-Pad26)") (class "Default")
      (node (ref "B1") (pin "26") (pinfunction "(OC0A/OC1C/PCINT7)_PB7_26") (pintype "passive"))
    )
    (net (code "41") (name "unconnected-(B1-(OC1A{slash}PCINT5)_PB5-Pad24)") (class "Default")
      (node (ref "B1") (pin "24") (pinfunction "(OC1A/PCINT5)_PB5_24") (pintype "passive"))
    )
    (net (code "42") (name "unconnected-(B1-(OC1B{slash}PCINT6)_PB6-Pad25)") (class "Default")
      (node (ref "B1") (pin "25") (pinfunction "(OC1B/PCINT6)_PB6_25") (pintype "passive"))
    )
    (net (code "43") (name "unconnected-(B1-(OC2A{slash}PCINT4)_PB4-Pad23)") (class "Default")
      (node (ref "B1") (pin "23") (pinfunction "(OC2A/PCINT4)_PB4_23") (pintype "passive"))
    )
    (net (code "44") (name "unconnected-(B1-(OC3A{slash}AIN1)_PE3-Pad5)") (class "Default")
      (node (ref "B1") (pin "5") (pinfunction "(OC3A/AIN1)_PE3_5") (pintype "passive"))
    )
    (net (code "45") (name "unconnected-(B1-(OC4A)_PH3-Pad15)") (class "Default")
      (node (ref "B1") (pin "15") (pinfunction "(OC4A)_PH3_15") (pintype "passive"))
    )
    (net (code "46") (name "unconnected-(B1-(OC4B)_PH4-Pad16)") (class "Default")
      (node (ref "B1") (pin "16") (pinfunction "(OC4B)_PH4_16") (pintype "passive"))
    )
    (net (code "47") (name "unconnected-(B1-(OC5A)_PL3-Pad38)") (class "Default")
      (node (ref "B1") (pin "38") (pinfunction "(OC5A)_PL3_38") (pintype "passive"))
    )
    (net (code "48") (name "unconnected-(B1-(OC5B)_PL4-Pad39)") (class "Default")
      (node (ref "B1") (pin "39") (pinfunction "(OC5B)_PL4_39") (pintype "passive"))
    )
    (net (code "49") (name "unconnected-(B1-(OC5C)_PL5-Pad40)") (class "Default")
      (node (ref "B1") (pin "40") (pinfunction "(OC5C)_PL5_40") (pintype "passive"))
    )
    (net (code "50") (name "unconnected-(B1-(RXD2)_PH0-Pad12)") (class "Default")
      (node (ref "B1") (pin "12") (pinfunction "(RXD2)_PH0_12") (pintype "passive"))
    )
    (net (code "51") (name "unconnected-(B1-(T0)_PD7-Pad50)") (class "Default")
      (node (ref "B1") (pin "50") (pinfunction "(T0)_PD7_50") (pintype "passive"))
    )
    (net (code "52") (name "unconnected-(B1-(T1)_PD6-Pad49)") (class "Default")
      (node (ref "B1") (pin "49") (pinfunction "(T1)_PD6_49") (pintype "passive"))
    )
    (net (code "53") (name "unconnected-(B1-(T3{slash}INT6)_PE6-Pad8)") (class "Default")
      (node (ref "B1") (pin "8") (pinfunction "(T3/INT6)_PE6_8") (pintype "passive"))
    )
    (net (code "54") (name "unconnected-(B1-(T4)_PH7-Pad27)") (class "Default")
      (node (ref "B1") (pin "27") (pinfunction "(T4)_PH7_27") (pintype "passive"))
    )
    (net (code "55") (name "unconnected-(B1-(T5)_PL2-Pad37)") (class "Default")
      (node (ref "B1") (pin "37") (pinfunction "(T5)_PL2_37") (pintype "passive"))
    )
    (net (code "56") (name "unconnected-(B1-(TOSC1)_PG4-Pad29)") (class "Default")
      (node (ref "B1") (pin "29") (pinfunction "(TOSC1)_PG4_29") (pintype "passive"))
    )
    (net (code "57") (name "unconnected-(B1-(TOSC2)_PG3-Pad28)") (class "Default")
      (node (ref "B1") (pin "28") (pinfunction "(TOSC2)_PG3_28") (pintype "passive"))
    )
    (net (code "58") (name "unconnected-(B1-(TXD2)_PH1-Pad13)") (class "Default")
      (node (ref "B1") (pin "13") (pinfunction "(TXD2)_PH1_13") (pintype "passive"))
    )
    (net (code "59") (name "unconnected-(B1-(XCK0{slash}AIN0)_PE2-Pad4)") (class "Default")
      (node (ref "B1") (pin "4") (pinfunction "(XCK0/AIN0)_PE2_4") (pintype "passive"))
    )
    (net (code "60") (name "unconnected-(B1-(XCK1)_PD5-Pad48)") (class "Default")
      (node (ref "B1") (pin "48") (pinfunction "(XCK1)_PD5_48") (pintype "passive"))
    )
    (net (code "61") (name "unconnected-(B1-(XCK2)_PH2-Pad14)") (class "Default")
      (node (ref "B1") (pin "14") (pinfunction "(XCK2)_PH2_14") (pintype "passive"))
    )
    (net (code "62") (name "unconnected-(B1-PA0_(AD0)-Pad78)") (class "Default")
      (node (ref "B1") (pin "78") (pinfunction "PA0_(AD0)_78") (pintype "passive"))
    )
    (net (code "63") (name "unconnected-(B1-PA1_(AD1)-Pad77)") (class "Default")
      (node (ref "B1") (pin "77") (pinfunction "PA1_(AD1)_77") (pintype "passive"))
    )
    (net (code "64") (name "unconnected-(B1-PA2_(AD2)-Pad76)") (class "Default")
      (node (ref "B1") (pin "76") (pinfunction "PA2_(AD2)_76") (pintype "passive"))
    )
    (net (code "65") (name "unconnected-(B1-PA3_(AD3)-Pad75)") (class "Default")
      (node (ref "B1") (pin "75") (pinfunction "PA3_(AD3)_75") (pintype "passive"))
    )
    (net (code "66") (name "unconnected-(B1-PA4_(AD4)-Pad74)") (class "Default")
      (node (ref "B1") (pin "74") (pinfunction "PA4_(AD4)_74") (pintype "passive"))
    )
    (net (code "67") (name "unconnected-(B1-PA5_(AD5)-Pad73)") (class "Default")
      (node (ref "B1") (pin "73") (pinfunction "PA5_(AD5)_73") (pintype "passive"))
    )
    (net (code "68") (name "unconnected-(B1-PA6_(AD6)-Pad72)") (class "Default")
      (node (ref "B1") (pin "72") (pinfunction "PA6_(AD6)_72") (pintype "passive"))
    )
    (net (code "69") (name "unconnected-(B1-PA7_(AD7)-Pad71)") (class "Default")
      (node (ref "B1") (pin "71") (pinfunction "PA7_(AD7)_71") (pintype "passive"))
    )
    (net (code "70") (name "unconnected-(B1-PC0_(A8)-Pad53)") (class "Default")
      (node (ref "B1") (pin "53") (pinfunction "PC0_(A8)_53") (pintype "passive"))
    )
    (net (code "71") (name "unconnected-(B1-PC1_(A9)-Pad54)") (class "Default")
      (node (ref "B1") (pin "54") (pinfunction "PC1_(A9)_54") (pintype "passive"))
    )
    (net (code "72") (name "unconnected-(B1-PC2_(A10)-Pad55)") (class "Default")
      (node (ref "B1") (pin "55") (pinfunction "PC2_(A10)_55") (pintype "passive"))
    )
    (net (code "73") (name "unconnected-(B1-PC3_(A11)-Pad56)") (class "Default")
      (node (ref "B1") (pin "56") (pinfunction "PC3_(A11)_56") (pintype "passive"))
    )
    (net (code "74") (name "unconnected-(B1-PC4_(A12)-Pad57)") (class "Default")
      (node (ref "B1") (pin "57") (pinfunction "PC4_(A12)_57") (pintype "passive"))
    )
    (net (code "75") (name "unconnected-(B1-PC5_(A13)-Pad58)") (class "Default")
      (node (ref "B1") (pin "58") (pinfunction "PC5_(A13)_58") (pintype "passive"))
    )
    (net (code "76") (name "unconnected-(B1-PC6_(A14)-Pad59)") (class "Default")
      (node (ref "B1") (pin "59") (pinfunction "PC6_(A14)_59") (pintype "passive"))
    )
    (net (code "77") (name "unconnected-(B1-PC7_(A15)-Pad60)") (class "Default")
      (node (ref "B1") (pin "60") (pinfunction "PC7_(A15)_60") (pintype "passive"))
    )
    (net (code "78") (name "unconnected-(B1-PF0_(ADC0)-Pad97)") (class "Default")
      (node (ref "B1") (pin "97") (pinfunction "PF0_(ADC0)_97") (pintype "passive"))
    )
    (net (code "79") (name "unconnected-(B1-PF1_(ADC1)-Pad96)") (class "Default")
      (node (ref "B1") (pin "96") (pinfunction "PF1_(ADC1)_96") (pintype "passive"))
    )
    (net (code "80") (name "unconnected-(B1-PF2_(ADC2)-Pad95)") (class "Default")
      (node (ref "B1") (pin "95") (pinfunction "PF2_(ADC2)_95") (pintype "passive"))
    )
    (net (code "81") (name "unconnected-(B1-PF3_(ADC3)-Pad94)") (class "Default")
      (node (ref "B1") (pin "94") (pinfunction "PF3_(ADC3)_94") (pintype "passive"))
    )
    (net (code "82") (name "unconnected-(B1-PF4_(ADC4{slash}TCK)-Pad93)") (class "Default")
      (node (ref "B1") (pin "93") (pinfunction "PF4_(ADC4/TCK)_93") (pintype "passive"))
    )
    (net (code "83") (name "unconnected-(B1-PF5_(ADC5{slash}TMS)-Pad92)") (class "Default")
      (node (ref "B1") (pin "92") (pinfunction "PF5_(ADC5/TMS)_92") (pintype "passive"))
    )
    (net (code "84") (name "unconnected-(B1-PF6_(ADC6{slash}TDO)-Pad91)") (class "Default")
      (node (ref "B1") (pin "91") (pinfunction "PF6_(ADC6/TDO)_91") (pintype "passive"))
    )
    (net (code "85") (name "unconnected-(B1-PF7_(ADC7{slash}TDI)-Pad90)") (class "Default")
      (node (ref "B1") (pin "90") (pinfunction "PF7_(ADC7/TDI)_90") (pintype "passive"))
    )
    (net (code "86") (name "unconnected-(B1-PG0_(~{WR)}-Pad51)") (class "Default")
      (node (ref "B1") (pin "51") (pinfunction "PG0_(~{WR)}_51") (pintype "passive"))
    )
    (net (code "87") (name "unconnected-(B1-PG1_(~{RD)}-Pad52)") (class "Default")
      (node (ref "B1") (pin "52") (pinfunction "PG1_(~{RD)}_52") (pintype "passive"))
    )
    (net (code "88") (name "unconnected-(B1-PG2_(ALE)-Pad70)") (class "Default")
      (node (ref "B1") (pin "70") (pinfunction "PG2_(ALE)_70") (pintype "passive"))
    )
    (net (code "89") (name "unconnected-(B1-PJ0_(RXD3{slash}PCINT9)-Pad63)") (class "Default")
      (node (ref "B1") (pin "63") (pinfunction "PJ0_(RXD3/PCINT9)_63") (pintype "passive"))
    )
    (net (code "90") (name "unconnected-(B1-PJ1_(TXD3{slash}PCINT10)-Pad64)") (class "Default")
      (node (ref "B1") (pin "64") (pinfunction "PJ1_(TXD3/PCINT10)_64") (pintype "passive"))
    )
    (net (code "91") (name "unconnected-(B1-PJ2_(XCK3{slash}PCINT11)-Pad65)") (class "Default")
      (node (ref "B1") (pin "65") (pinfunction "PJ2_(XCK3/PCINT11)_65") (pintype "passive"))
    )
    (net (code "92") (name "unconnected-(B1-PJ3_(PCINT12)-Pad66)") (class "Default")
      (node (ref "B1") (pin "66") (pinfunction "PJ3_(PCINT12)_66") (pintype "passive"))
    )
    (net (code "93") (name "unconnected-(B1-PJ4_(PCINT13)-Pad67)") (class "Default")
      (node (ref "B1") (pin "67") (pinfunction "PJ4_(PCINT13)_67") (pintype "passive"))
    )
    (net (code "94") (name "unconnected-(B1-PJ5_(PCINT14)-Pad68)") (class "Default")
      (node (ref "B1") (pin "68") (pinfunction "PJ5_(PCINT14)_68") (pintype "passive"))
    )
    (net (code "95") (name "unconnected-(B1-PJ6_(PCINT15)-Pad69)") (class "Default")
      (node (ref "B1") (pin "69") (pinfunction "PJ6_(PCINT15)_69") (pintype "passive"))
    )
    (net (code "96") (name "unconnected-(B1-PJ7-Pad79)") (class "Default")
      (node (ref "B1") (pin "79") (pinfunction "PJ7_79") (pintype "passive"))
    )
    (net (code "97") (name "unconnected-(B1-PK0_(ADC8{slash}PCINT16)-Pad89)") (class "Default")
      (node (ref "B1") (pin "89") (pinfunction "PK0_(ADC8/PCINT16)_89") (pintype "passive"))
    )
    (net (code "98") (name "unconnected-(B1-PK1_(ADC9{slash}PCINT17)-Pad88)") (class "Default")
      (node (ref "B1") (pin "88") (pinfunction "PK1_(ADC9/PCINT17)_88") (pintype "passive"))
    )
    (net (code "99") (name "unconnected-(B1-PK2_(ADC10{slash}PCINT18)-Pad87)") (class "Default")
      (node (ref "B1") (pin "87") (pinfunction "PK2_(ADC10/PCINT18)_87") (pintype "passive"))
    )
    (net (code "100") (name "unconnected-(B1-PK3_(ADC11{slash}PCINT19)-Pad86)") (class "Default")
      (node (ref "B1") (pin "86") (pinfunction "PK3_(ADC11/PCINT19)_86") (pintype "passive"))
    )
    (net (code "101") (name "unconnected-(B1-PK4_(ADC12{slash}PCINT20)-Pad85)") (class "Default")
      (node (ref "B1") (pin "85") (pinfunction "PK4_(ADC12/PCINT20)_85") (pintype "passive"))
    )
    (net (code "102") (name "unconnected-(B1-PK5_(ADC13{slash}PCINT21)-Pad84)") (class "Default")
      (node (ref "B1") (pin "84") (pinfunction "PK5_(ADC13/PCINT21)_84") (pintype "passive"))
    )
    (net (code "103") (name "unconnected-(B1-PK6_(ADC14{slash}PCINT22)-Pad83)") (class "Default")
      (node (ref "B1") (pin "83") (pinfunction "PK6_(ADC14/PCINT22)_83") (pintype "passive"))
    )
    (net (code "104") (name "unconnected-(B1-PK7_(ADC15{slash}PCINT23)-Pad82)") (class "Default")
      (node (ref "B1") (pin "82") (pinfunction "PK7_(ADC15/PCINT23)_82") (pintype "passive"))
    )
    (net (code "105") (name "unconnected-(B1-PL6-Pad41)") (class "Default")
      (node (ref "B1") (pin "41") (pinfunction "PL6_41") (pintype "passive"))
    )
    (net (code "106") (name "unconnected-(B1-PL7-Pad42)") (class "Default")
      (node (ref "B1") (pin "42") (pinfunction "PL7_42") (pintype "passive"))
    )
    (net (code "107") (name "unconnected-(CN1-Pad6)") (class "Default")
      (node (ref "CN1") (pin "6") (pinfunction "6_6") (pintype "passive+no_connect"))
    )
    (net (code "108") (name "unconnected-(CN2-Pad6)") (class "Default")
      (node (ref "CN2") (pin "6") (pinfunction "6_6") (pintype "passive+no_connect"))
    )
    (net (code "109") (name "unconnected-(J3-Pad3)") (class "Default")
      (node (ref "J3") (pin "3") (pinfunction "3_3") (pintype "passive"))
    )
    (net (code "110") (name "unconnected-(J3-PadMH1)") (class "Default")
      (node (ref "J3") (pin "MH1") (pinfunction "MH1_MH1") (pintype "passive"))
    )
    (net (code "111") (name "unconnected-(J3-PadMH2)") (class "Default")
      (node (ref "J3") (pin "MH2") (pinfunction "MH2_MH2") (pintype "passive"))
    )
    (net (code "112") (name "unconnected-(J4-CC1-PadA5)") (class "Default")
      (node (ref "J4") (pin "A5") (pinfunction "CC1_A5") (pintype "passive+no_connect"))
    )
    (net (code "113") (name "unconnected-(J4-CC2-PadB5)") (class "Default")
      (node (ref "J4") (pin "B5") (pinfunction "CC2_B5") (pintype "passive+no_connect"))
    )
    (net (code "114") (name "unconnected-(J4-SBU1-PadA8)") (class "Default")
      (node (ref "J4") (pin "A8") (pinfunction "SBU1_A8") (pintype "passive+no_connect"))
    )
    (net (code "115") (name "unconnected-(J4-SBU2-PadB8)") (class "Default")
      (node (ref "J4") (pin "B8") (pinfunction "SBU2_B8") (pintype "passive+no_connect"))
    )
    (net (code "116") (name "unconnected-(J4-SHIELD-PadSH)") (class "Default")
      (node (ref "J4") (pin "SH") (pinfunction "SHIELD_SH") (pintype "passive+no_connect"))
    )
    (net (code "117") (name "unconnected-(RN1-Pad3)") (class "Default")
      (node (ref "RN1") (pin "3") (pinfunction "3_3") (pintype "passive+no_connect"))
    )
    (net (code "118") (name "unconnected-(RN1-Pad4)") (class "Default")
      (node (ref "RN1") (pin "4") (pinfunction "4_4") (pintype "passive+no_connect"))
    )
    (net (code "119") (name "unconnected-(SW1-Pad4)") (class "Default")
      (node (ref "SW1") (pin "4") (pinfunction "4_4") (pintype "passive"))
    )
    (net (code "120") (name "unconnected-(SW1-Pad5)") (class "Default")
      (node (ref "SW1") (pin "5") (pinfunction "5_5") (pintype "passive"))
    )
    (net (code "121") (name "unconnected-(U2-32kHz-Pad1)") (class "Default")
      (node (ref "U2") (pin "1") (pinfunction "32kHz_1") (pintype "passive+no_connect"))
    )
    (net (code "122") (name "unconnected-(U2-INT#{slash}SQW-Pad3)") (class "Default")
      (node (ref "U2") (pin "3") (pinfunction "INT#/SQW_3") (pintype "passive+no_connect"))
    )
    (net (code "123") (name "unconnected-(U2-RST#-Pad4)") (class "Default")
      (node (ref "U2") (pin "4") (pinfunction "RST#_4") (pintype "passive+no_connect"))
    )
    (net (code "124") (name "unconnected-(U3-CTS#-Pad9)") (class "Default")
      (node (ref "U3") (pin "9") (pinfunction "CTS#_9") (pintype "passive+no_connect"))
    )
    (net (code "125") (name "unconnected-(U3-DCD#-Pad12)") (class "Default")
      (node (ref "U3") (pin "12") (pinfunction "DCD#_12") (pintype "passive+no_connect"))
    )
    (net (code "126") (name "unconnected-(U3-DSR#-Pad10)") (class "Default")
      (node (ref "U3") (pin "10") (pinfunction "DSR#_10") (pintype "passive+no_connect"))
    )
    (net (code "127") (name "unconnected-(U3-NC.-Pad7)") (class "Default")
      (node (ref "U3") (pin "7") (pinfunction "NC._7") (pintype "passive+no_connect"))
    )
    (net (code "128") (name "unconnected-(U3-OUT#-Pad8)") (class "Default")
      (node (ref "U3") (pin "8") (pinfunction "OUT#_8") (pintype "passive+no_connect"))
    )
    (net (code "129") (name "unconnected-(U3-R232-Pad15)") (class "Default")
      (node (ref "U3") (pin "15") (pinfunction "R232_15") (pintype "passive+no_connect"))
    )
    (net (code "130") (name "unconnected-(U3-RI#-Pad11)") (class "Default")
      (node (ref "U3") (pin "11") (pinfunction "RI#_11") (pintype "passive+no_connect"))
    )
    (net (code "131") (name "unconnected-(U3-RTS#-Pad14)") (class "Default")
      (node (ref "U3") (pin "14") (pinfunction "RTS#_14") (pintype "passive+no_connect"))
    )
    (net (code "132") (name "unconnected-(U3-V3-Pad4)") (class "Default")
      (node (ref "U3") (pin "4") (pinfunction "V3_4") (pintype "passive+no_connect"))
    )
  )
)
